# 09_-_SD_CARD.net
KiCad netlist of a schematic drawn in Altium Designer
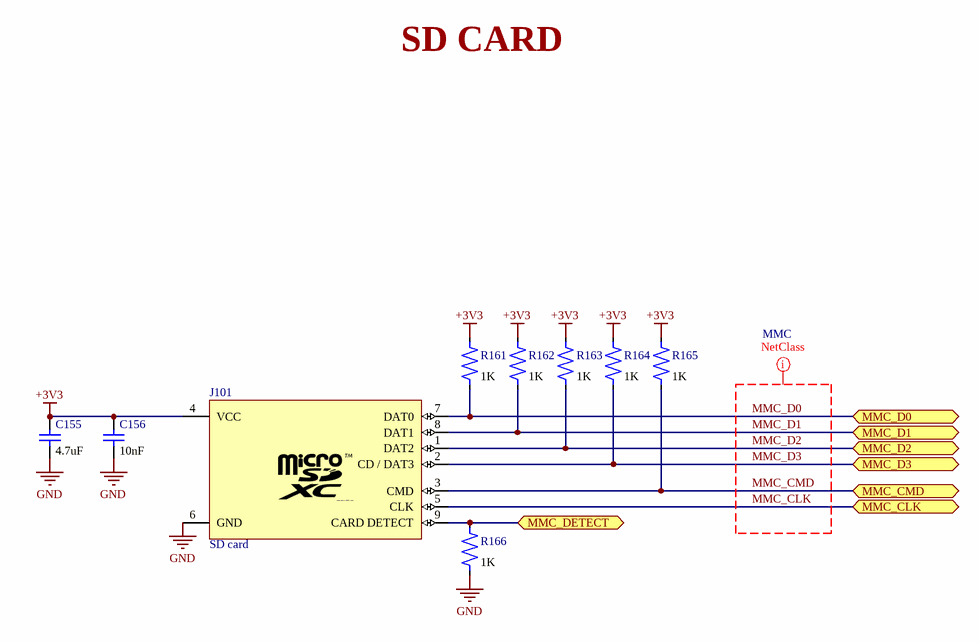
[diagram p0: [09] - SD CARD.SchDoc]

(export (version "E")
  (design (tool "Eeschema 10.0.6"))
  (components
    (comp (ref "C155")
      (value "4.7uF")
      (footprint "C0603")
      (description "C0603")
      (fields (field (name "Comment") "02016D104KAT2A"))
      (libsource (lib "Passive components") (part "02016D104KAT2A"))
    )
    (comp (ref "C156")
      (value "10nF")
      (footprint "C0402")
      (description "C0402")
      (fields (field (name "Comment") "04023C103KAT2A"))
      (libsource (lib "Passive components") (part "04023C103KAT2A"))
    )
    (comp (ref "J101")
      (value "SD card")
      (footprint "SD card push push")
      (description "SD micro card push push")
      (libsource (lib "Connectors") (part "47219-2001_1"))
    )
    (comp (ref "R161")
      (value "1K")
      (footprint "R0402")
      (description "R0402")
      (fields (field (name "Comment") "CRCW04020000Z0ED"))
      (libsource (lib "Passive components") (part "CRCW04020000Z0ED"))
    )
    (comp (ref "R162")
      (value "1K")
      (footprint "R0402")
      (description "R0402")
      (fields (field (name "Comment") "CRCW04020000Z0ED"))
      (libsource (lib "Passive components") (part "CRCW04020000Z0ED"))
    )
    (comp (ref "R163")
      (value "1K")
      (footprint "R0402")
      (description "R0402")
      (fields (field (name "Comment") "CRCW04020000Z0ED"))
      (libsource (lib "Passive components") (part "CRCW04020000Z0ED"))
    )
    (comp (ref "R164")
      (value "1K")
      (footprint "R0402")
      (description "R0402")
      (fields (field (name "Comment") "CRCW04020000Z0ED"))
      (libsource (lib "Passive components") (part "CRCW04020000Z0ED"))
    )
    (comp (ref "R165")
      (value "1K")
      (footprint "R0402")
      (description "R0402")
      (fields (field (name "Comment") "CRCW04020000Z0ED"))
      (libsource (lib "Passive components") (part "CRCW04020000Z0ED"))
    )
    (comp (ref "R166")
      (value "1K")
      (footprint "R0402")
      (description "R0402")
      (fields (field (name "Comment") "CRCW04020000Z0ED"))
      (libsource (lib "Passive components") (part "CRCW04020000Z0ED"))
    )
  )
  (nets
    (net (code "1") (name "+3V3") (class "Default")
      (node (ref "C155") (pin "2") (pinfunction "2_2") (pintype "passive"))
      (node (ref "C156") (pin "2") (pinfunction "2_2") (pintype "passive"))
      (node (ref "J101") (pin "4") (pinfunction "VCC_4") (pintype "power_in"))
      (node (ref "R161") (pin "2") (pinfunction "3_2") (pintype "passive"))
      (node (ref "R162") (pin "2") (pinfunction "3_2") (pintype "passive"))
      (node (ref "R163") (pin "2") (pinfunction "3_2") (pintype "passive"))
      (node (ref "R164") (pin "2") (pinfunction "3_2") (pintype "passive"))
      (node (ref "R165") (pin "2") (pinfunction "3_2") (pintype "passive"))
    )
    (net (code "2") (name "/MMC_CLK") (class "Default")
      (node (ref "J101") (pin "5") (pinfunction "CLK_5") (pintype "bidirectional"))
    )
    (net (code "3") (name "/MMC_CMD") (class "Default")
      (node (ref "J101") (pin "3") (pinfunction "CMD_3") (pintype "bidirectional"))
      (node (ref "R165") (pin "1") (pinfunction "1_1") (pintype "passive"))
    )
    (net (code "4") (name "/MMC_D0") (class "Default")
      (node (ref "J101") (pin "7") (pinfunction "DAT0_7") (pintype "bidirectional"))
      (node (ref "R161") (pin "1") (pinfunction "1_1") (pintype "passive"))
    )
    (net (code "5") (name "/MMC_D1") (class "Default")
      (node (ref "J101") (pin "8") (pinfunction "DAT1_8") (pintype "bidirectional"))
      (node (ref "R162") (pin "1") (pinfunction "1_1") (pintype "passive"))
    )
    (net (code "6") (name "/MMC_D2") (class "Default")
      (node (ref "J101") (pin "1") (pinfunction "DAT2_1") (pintype "bidirectional"))
      (node (ref "R163") (pin "1") (pinfunction "1_1") (pintype "passive"))
    )
    (net (code "7") (name "/MMC_D3") (class "Default")
      (node (ref "J101") (pin "2") (pinfunction "CD_/_DAT3_2") (pintype "bidirectional"))
      (node (ref "R164") (pin "1") (pinfunction "1_1") (pintype "passive"))
    )
    (net (code "8") (name "/MMC_DETECT") (class "Default")
      (node (ref "J101") (pin "9") (pinfunction "CARD_DETECT_9") (pintype "bidirectional"))
      (node (ref "R166") (pin "2") (pinfunction "3_2") (pintype "passive"))
    )
    (net (code "9") (name "GND") (class "Default")
      (node (ref "C155") (pin "1") (pinfunction "1_1") (pintype "passive"))
      (node (ref "C156") (pin "1") (pinfunction "1_1") (pintype "passive"))
      (node (ref "J101") (pin "6") (pinfunction "GND_6") (pintype "power_in"))
      (node (ref "R166") (pin "1") (pinfunction "1_1") (pintype "passive"))
    )
  )
)
